# SuperGreatPI_v03.net
KiCad netlist of a schematic drawn in EAGLE
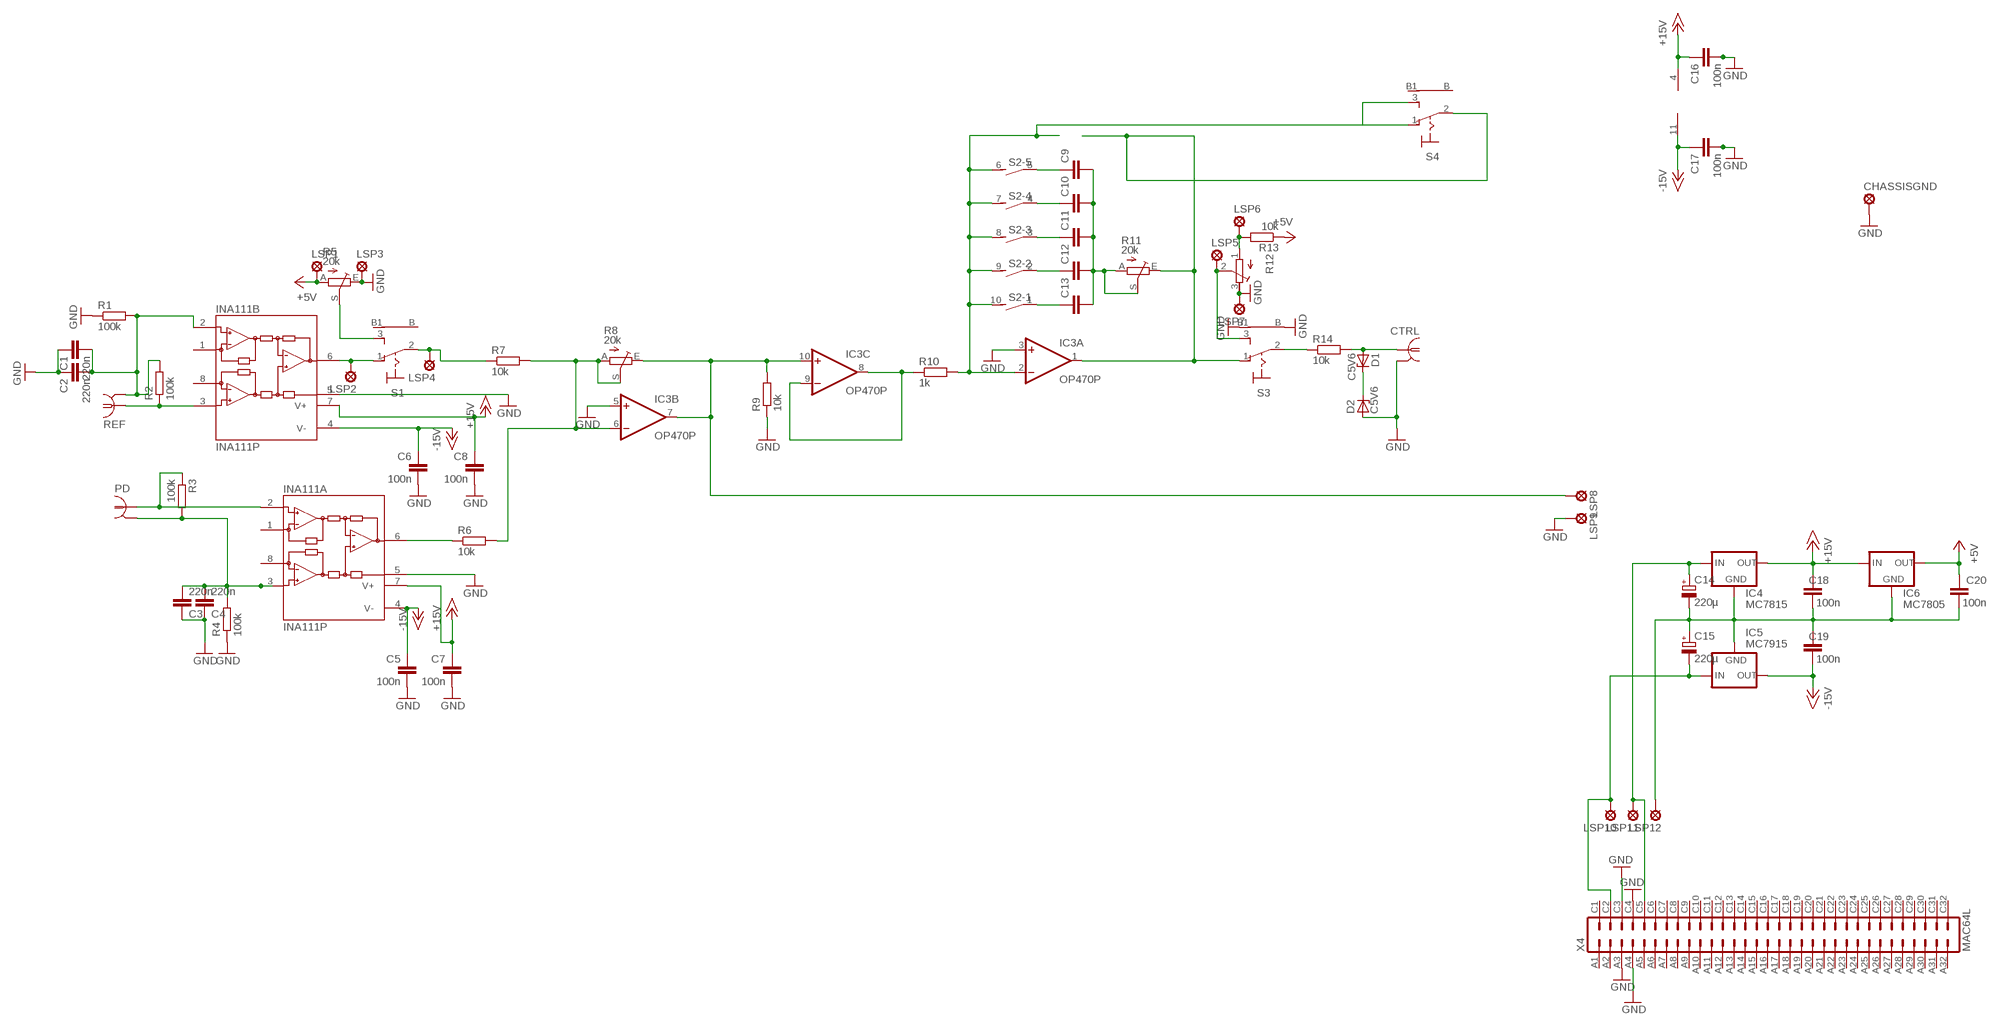
[diagram p0: schematic, sheet 1]

(export (version "E")
  (design (tool "Eeschema 10.0.6"))
  (components
    (comp (ref "C1")
      (value "220n")
      (footprint "eagle-import:C025-024X044")
      (libsource (lib "eagle-import") (part "C-EU025-024X044"))
    )
    (comp (ref "C2")
      (value "220n")
      (footprint "eagle-import:C025-024X044")
      (libsource (lib "eagle-import") (part "C-EU025-024X044"))
    )
    (comp (ref "C3")
      (value "220n")
      (footprint "eagle-import:C025-024X044")
      (libsource (lib "eagle-import") (part "C-EU025-024X044"))
    )
    (comp (ref "C4")
      (value "220n")
      (footprint "eagle-import:C025-024X044")
      (libsource (lib "eagle-import") (part "C-EU025-024X044"))
    )
    (comp (ref "C5")
      (value "100n")
      (footprint "eagle-import:C025-024X044")
      (libsource (lib "eagle-import") (part "C-EU025-024X044"))
    )
    (comp (ref "C6")
      (value "100n")
      (footprint "eagle-import:C025-024X044")
      (libsource (lib "eagle-import") (part "C-EU025-024X044"))
    )
    (comp (ref "C7")
      (value "100n")
      (footprint "eagle-import:C025-024X044")
      (libsource (lib "eagle-import") (part "C-EU025-024X044"))
    )
    (comp (ref "C8")
      (value "100n")
      (footprint "eagle-import:C025-024X044")
      (libsource (lib "eagle-import") (part "C-EU025-024X044"))
    )
    (comp (ref "C9")
      (value "C-EU050-025X075")
      (footprint "eagle-import:C050-025X075")
      (libsource (lib "eagle-import") (part "C-EU050-025X075"))
    )
    (comp (ref "C10")
      (value "C-EU050-025X075")
      (footprint "eagle-import:C050-025X075")
      (libsource (lib "eagle-import") (part "C-EU050-025X075"))
    )
    (comp (ref "C11")
      (value "C-EU050-025X075")
      (footprint "eagle-import:C050-025X075")
      (libsource (lib "eagle-import") (part "C-EU050-025X075"))
    )
    (comp (ref "C12")
      (value "C-EU050-025X075")
      (footprint "eagle-import:C050-025X075")
      (libsource (lib "eagle-import") (part "C-EU050-025X075"))
    )
    (comp (ref "C13")
      (value "C-EU050-025X075")
      (footprint "eagle-import:C050-025X075")
      (libsource (lib "eagle-import") (part "C-EU050-025X075"))
    )
    (comp (ref "C14")
      (value "220µ")
      (footprint "eagle-import:E3,5-8")
      (libsource (lib "eagle-import") (part "CPOL-EUE3.5-8"))
    )
    (comp (ref "C15")
      (value "220µ")
      (footprint "eagle-import:E3,5-8")
      (libsource (lib "eagle-import") (part "CPOL-EUE3.5-8"))
    )
    (comp (ref "C16")
      (value "100n")
      (footprint "eagle-import:C025-024X044")
      (libsource (lib "eagle-import") (part "C-EU025-024X044"))
    )
    (comp (ref "C17")
      (value "100n")
      (footprint "eagle-import:C025-024X044")
      (libsource (lib "eagle-import") (part "C-EU025-024X044"))
    )
    (comp (ref "C18")
      (value "100n")
      (footprint "eagle-import:C025-024X044")
      (libsource (lib "eagle-import") (part "C-EU025-024X044"))
    )
    (comp (ref "C19")
      (value "100n")
      (footprint "eagle-import:C025-024X044")
      (libsource (lib "eagle-import") (part "C-EU025-024X044"))
    )
    (comp (ref "C20")
      (value "100n")
      (footprint "eagle-import:C025-024X044")
      (libsource (lib "eagle-import") (part "C-EU025-024X044"))
    )
    (comp (ref "CHASSISGND")
      (value "MCS08")
      (footprint "eagle-import:MCS08")
      (libsource (lib "eagle-import") (part "MCS08"))
    )
    (comp (ref "CTRL")
      (value "1-227161-0")
      (footprint "eagle-import:AMP_227161")
      (libsource (lib "eagle-import") (part "?2271611--0"))
    )
    (comp (ref "D1")
      (value "C5V6")
      (footprint "eagle-import:DO34Z7")
      (libsource (lib "eagle-import") (part "BZX90"))
    )
    (comp (ref "D2")
      (value "C5V6")
      (footprint "eagle-import:DO34Z7")
      (libsource (lib "eagle-import") (part "BZX90"))
    )
    (comp (ref "IC3")
      (value "OP470P")
      (footprint "eagle-import:DIL14")
      (libsource (lib "eagle-import") (part "OP470P"))
    )
    (comp (ref "IC4")
      (value "MC7815")
      (footprint "eagle-import:78XXS")
      (libsource (lib "eagle-import") (part "78XXS"))
    )
    (comp (ref "IC5")
      (value "MC7915")
      (footprint "eagle-import:79XXS")
      (libsource (lib "eagle-import") (part "79XXS"))
    )
    (comp (ref "IC6")
      (value "MC7805")
      (footprint "eagle-import:78XXS")
      (libsource (lib "eagle-import") (part "78XXS"))
    )
    (comp (ref "INA111A")
      (value "INA111P")
      (footprint "eagle-import:DIL08")
      (libsource (lib "eagle-import") (part "INA111P"))
    )
    (comp (ref "INA111B")
      (value "INA111P")
      (footprint "eagle-import:DIL08")
      (libsource (lib "eagle-import") (part "INA111P"))
    )
    (comp (ref "LSP1")
      (value "MCS08")
      (footprint "eagle-import:MCS08")
      (libsource (lib "eagle-import") (part "MCS08"))
    )
    (comp (ref "LSP2")
      (value "MCS08")
      (footprint "eagle-import:MCS08")
      (libsource (lib "eagle-import") (part "MCS08"))
    )
    (comp (ref "LSP3")
      (value "MCS08")
      (footprint "eagle-import:MCS08")
      (libsource (lib "eagle-import") (part "MCS08"))
    )
    (comp (ref "LSP4")
      (value "MCS08")
      (footprint "eagle-import:MCS08")
      (libsource (lib "eagle-import") (part "MCS08"))
    )
    (comp (ref "LSP5")
      (value "MCS08")
      (footprint "eagle-import:MCS08")
      (libsource (lib "eagle-import") (part "MCS08"))
    )
    (comp (ref "LSP6")
      (value "MCS08")
      (footprint "eagle-import:MCS08")
      (libsource (lib "eagle-import") (part "MCS08"))
    )
    (comp (ref "LSP7")
      (value "MCS08")
      (footprint "eagle-import:MCS08")
      (libsource (lib "eagle-import") (part "MCS08"))
    )
    (comp (ref "LSP8")
      (value "MCS08")
      (footprint "eagle-import:MCS08")
      (libsource (lib "eagle-import") (part "MCS08"))
    )
    (comp (ref "LSP9")
      (value "MCS08")
      (footprint "eagle-import:MCS08")
      (libsource (lib "eagle-import") (part "MCS08"))
    )
    (comp (ref "LSP10")
      (value "-18V")
      (footprint "eagle-import:MCS08")
      (libsource (lib "eagle-import") (part "MCS08"))
    )
    (comp (ref "LSP11")
      (value "-18V")
      (footprint "eagle-import:MCS08")
      (libsource (lib "eagle-import") (part "MCS08"))
    )
    (comp (ref "LSP12")
      (value "GND")
      (footprint "eagle-import:MCS08")
      (libsource (lib "eagle-import") (part "MCS08"))
    )
    (comp (ref "PD")
      (value "1-227161-0")
      (footprint "eagle-import:AMP_227161")
      (libsource (lib "eagle-import") (part "?2271611--0"))
    )
    (comp (ref "R1")
      (value "100k")
      (footprint "eagle-import:0207_2V")
      (libsource (lib "eagle-import") (part "R-EU_0207/2V"))
    )
    (comp (ref "R2")
      (value "100k")
      (footprint "eagle-import:0207_2V")
      (libsource (lib "eagle-import") (part "R-EU_0207/2V"))
    )
    (comp (ref "R3")
      (value "100k")
      (footprint "eagle-import:0207_2V")
      (libsource (lib "eagle-import") (part "R-EU_0207/2V"))
    )
    (comp (ref "R4")
      (value "100k")
      (footprint "eagle-import:0207_2V")
      (libsource (lib "eagle-import") (part "R-EU_0207/2V"))
    )
    (comp (ref "R5")
      (value "20k")
      (footprint "eagle-import:PT-SPIN")
      (libsource (lib "eagle-import") (part "TRIM_EU-PTSPIN"))
    )
    (comp (ref "R6")
      (value "10k")
      (footprint "eagle-import:0207_10")
      (libsource (lib "eagle-import") (part "R-EU_0207/10"))
    )
    (comp (ref "R7")
      (value "10k")
      (footprint "eagle-import:0207_10")
      (libsource (lib "eagle-import") (part "R-EU_0207/10"))
    )
    (comp (ref "R8")
      (value "20k")
      (footprint "eagle-import:PT-SPIN")
      (libsource (lib "eagle-import") (part "TRIM_EU-PTSPIN"))
    )
    (comp (ref "R9")
      (value "10k")
      (footprint "eagle-import:0207_10")
      (libsource (lib "eagle-import") (part "R-EU_0207/10"))
    )
    (comp (ref "R10")
      (value "1k")
      (footprint "eagle-import:0207_10")
      (libsource (lib "eagle-import") (part "R-EU_0207/10"))
    )
    (comp (ref "R11")
      (value "20k")
      (footprint "eagle-import:PT-SPIN")
      (libsource (lib "eagle-import") (part "TRIM_EU-PTSPIN"))
    )
    (comp (ref "R12")
      (value "R-TRIMM3299W")
      (footprint "eagle-import:RTRIM3299W")
      (libsource (lib "eagle-import") (part "R-TRIMM3299W"))
    )
    (comp (ref "R13")
      (value "10k")
      (footprint "eagle-import:0207_10")
      (libsource (lib "eagle-import") (part "R-EU_0207/10"))
    )
    (comp (ref "R14")
      (value "10k")
      (footprint "eagle-import:0207_10")
      (libsource (lib "eagle-import") (part "R-EU_0207/10"))
    )
    (comp (ref "REF")
      (value "1-227161-0")
      (footprint "eagle-import:AMP_227161")
      (libsource (lib "eagle-import") (part "?2271611--0"))
    )
    (comp (ref "S1")
      (value "LPV-1")
      (footprint "eagle-import:LPV-1")
      (libsource (lib "eagle-import") (part "LPV-1"))
    )
    (comp (ref "S2")
      (value "DS05E")
      (footprint "eagle-import:DS-05")
      (libsource (lib "eagle-import") (part "DS05E"))
    )
    (comp (ref "S3")
      (value "LPV-1")
      (footprint "eagle-import:LPV-1")
      (libsource (lib "eagle-import") (part "LPV-1"))
    )
    (comp (ref "S4")
      (value "LPV-1")
      (footprint "eagle-import:LPV-1")
      (libsource (lib "eagle-import") (part "switch_380_LPV-1"))
    )
    (comp (ref "X4")
      (value "MAC64L")
      (footprint "eagle-import:MAC64L")
      (libsource (lib "eagle-import") (part "MAC64L"))
    )
  )
  (nets
    (net (code "1") (name "+5V") (class "Default")
      (node (ref "C20") (pin "1") (pinfunction "1_1") (pintype "passive"))
      (node (ref "IC6") (pin "OUT") (pinfunction "OUT_OUT") (pintype "passive"))
      (node (ref "LSP1") (pin "MP") (pinfunction "MP_MP") (pintype "passive"))
      (node (ref "R13") (pin "1") (pinfunction "1_1") (pintype "passive"))
      (node (ref "R5") (pin "A") (pinfunction "A_A") (pintype "passive"))
    )
    (net (code "2") (name "+15V") (class "Default")
      (node (ref "C16") (pin "1") (pinfunction "1_1") (pintype "passive"))
      (node (ref "C18") (pin "1") (pinfunction "1_1") (pintype "passive"))
      (node (ref "C7") (pin "1") (pinfunction "1_1") (pintype "passive"))
      (node (ref "C8") (pin "1") (pinfunction "1_1") (pintype "passive"))
      (node (ref "IC3") (pin "4") (pinfunction "V+_4") (pintype "power_in"))
      (node (ref "IC4") (pin "OUT") (pinfunction "OUT_OUT") (pintype "passive"))
      (node (ref "IC6") (pin "IN") (pinfunction "IN_IN") (pintype "input"))
      (node (ref "INA111A") (pin "7") (pinfunction "V+_7") (pintype "power_in"))
      (node (ref "INA111B") (pin "7") (pinfunction "V+_7") (pintype "power_in"))
    )
    (net (code "3") (name "-15V") (class "Default")
      (node (ref "C17") (pin "1") (pinfunction "1_1") (pintype "passive"))
      (node (ref "C19") (pin "2") (pinfunction "2_2") (pintype "passive"))
      (node (ref "C5") (pin "1") (pinfunction "1_1") (pintype "passive"))
      (node (ref "C6") (pin "1") (pinfunction "1_1") (pintype "passive"))
      (node (ref "IC3") (pin "11") (pinfunction "V-_11") (pintype "power_in"))
      (node (ref "IC5") (pin "OUT") (pinfunction "OUT_OUT") (pintype "passive"))
      (node (ref "INA111A") (pin "4") (pinfunction "V-_4") (pintype "power_in"))
      (node (ref "INA111B") (pin "4") (pinfunction "V-_4") (pintype "power_in"))
    )
    (net (code "4") (name "GND") (class "Default")
      (node (ref "C1") (pin "1") (pinfunction "1_1") (pintype "passive"))
      (node (ref "C14") (pin "-") (pinfunction "-_-") (pintype "passive"))
      (node (ref "C15") (pin "+") (pinfunction "+_+") (pintype "passive"))
      (node (ref "C16") (pin "2") (pinfunction "2_2") (pintype "passive"))
      (node (ref "C17") (pin "2") (pinfunction "2_2") (pintype "passive"))
      (node (ref "C18") (pin "2") (pinfunction "2_2") (pintype "passive"))
      (node (ref "C19") (pin "1") (pinfunction "1_1") (pintype "passive"))
      (node (ref "C2") (pin "1") (pinfunction "1_1") (pintype "passive"))
      (node (ref "C20") (pin "2") (pinfunction "2_2") (pintype "passive"))
      (node (ref "C3") (pin "1") (pinfunction "1_1") (pintype "passive"))
      (node (ref "C4") (pin "1") (pinfunction "1_1") (pintype "passive"))
      (node (ref "C5") (pin "2") (pinfunction "2_2") (pintype "passive"))
      (node (ref "C6") (pin "2") (pinfunction "2_2") (pintype "passive"))
      (node (ref "C7") (pin "2") (pinfunction "2_2") (pintype "passive"))
      (node (ref "C8") (pin "2") (pinfunction "2_2") (pintype "passive"))
      (node (ref "CHASSISGND") (pin "MP") (pinfunction "MP_MP") (pintype "passive"))
      (node (ref "CTRL") (pin "2") (pinfunction "GND_2") (pintype "power_in"))
      (node (ref "D2") (pin "A") (pinfunction "A_A") (pintype "passive"))
      (node (ref "IC3") (pin "3") (pinfunction "+IN_3") (pintype "input"))
      (node (ref "IC3") (pin "5") (pinfunction "+IN_5") (pintype "input"))
      (node (ref "IC4") (pin "GND") (pinfunction "GND_GND") (pintype "input"))
      (node (ref "IC5") (pin "GND") (pinfunction "GND_GND") (pintype "input"))
      (node (ref "IC6") (pin "GND") (pinfunction "GND_GND") (pintype "input"))
      (node (ref "INA111A") (pin "5") (pinfunction "REF_5") (pintype "passive"))
      (node (ref "INA111B") (pin "5") (pinfunction "REF_5") (pintype "passive"))
      (node (ref "LSP12") (pin "MP") (pinfunction "MP_MP") (pintype "passive"))
      (node (ref "LSP3") (pin "MP") (pinfunction "MP_MP") (pintype "passive"))
      (node (ref "LSP7") (pin "MP") (pinfunction "MP_MP") (pintype "passive"))
      (node (ref "LSP9") (pin "MP") (pinfunction "MP_MP") (pintype "passive"))
      (node (ref "R1") (pin "1") (pinfunction "1_1") (pintype "passive"))
      (node (ref "R12") (pin "3") (pinfunction "E_3") (pintype "passive"))
      (node (ref "R4") (pin "1") (pinfunction "1_1") (pintype "passive"))
      (node (ref "R5") (pin "E") (pinfunction "E_E") (pintype "passive"))
      (node (ref "R9") (pin "1") (pinfunction "1_1") (pintype "passive"))
      (node (ref "S3") (pin "B") (pinfunction "B_B") (pintype "passive"))
      (node (ref "S3") (pin "B1") (pinfunction "B1_B1") (pintype "passive"))
      (node (ref "X4") (pin "A3") (pinfunction "A3_A3") (pintype "passive"))
      (node (ref "X4") (pin "A4") (pinfunction "A4_A4") (pintype "passive"))
      (node (ref "X4") (pin "C3") (pinfunction "C3_C3") (pintype "passive"))
      (node (ref "X4") (pin "C4") (pinfunction "C4_C4") (pintype "passive"))
    )
    (net (code "5") (name "Net-(C10-Pad2)") (class "Default")
      (node (ref "C10") (pin "2") (pinfunction "2_2") (pintype "passive"))
      (node (ref "C11") (pin "2") (pinfunction "2_2") (pintype "passive"))
      (node (ref "C12") (pin "2") (pinfunction "2_2") (pintype "passive"))
      (node (ref "C13") (pin "2") (pinfunction "2_2") (pintype "passive"))
      (node (ref "C9") (pin "2") (pinfunction "2_2") (pintype "passive"))
      (node (ref "R11") (pin "A") (pinfunction "A_A") (pintype "passive"))
      (node (ref "R11") (pin "S") (pinfunction "S_S") (pintype "passive"))
    )
    (net (code "6") (name "Net-(C13-Pad1)") (class "Default")
      (node (ref "C13") (pin "1") (pinfunction "1_1") (pintype "passive"))
      (node (ref "S2") (pin "1") (pinfunction "1_1") (pintype "passive"))
    )
    (net (code "7") (name "Net-(C14-Pad+)") (class "Default")
      (node (ref "C14") (pin "+") (pinfunction "+_+") (pintype "passive"))
      (node (ref "IC4") (pin "IN") (pinfunction "IN_IN") (pintype "input"))
      (node (ref "LSP11") (pin "MP") (pinfunction "MP_MP") (pintype "passive"))
      (node (ref "X4") (pin "C5") (pinfunction "C5_C5") (pintype "passive"))
    )
    (net (code "8") (name "Net-(C15-Pad-)") (class "Default")
      (node (ref "C15") (pin "-") (pinfunction "-_-") (pintype "passive"))
      (node (ref "IC5") (pin "IN") (pinfunction "IN_IN") (pintype "input"))
      (node (ref "LSP10") (pin "MP") (pinfunction "MP_MP") (pintype "passive"))
      (node (ref "X4") (pin "C2") (pinfunction "C2_C2") (pintype "passive"))
    )
    (net (code "9") (name "Net-(CTRL-Pad1)") (class "Default")
      (node (ref "CTRL") (pin "1") (pinfunction "1_1") (pintype "passive"))
      (node (ref "D1") (pin "A") (pinfunction "A_A") (pintype "passive"))
      (node (ref "R14") (pin "2") (pinfunction "2_2") (pintype "passive"))
    )
    (net (code "10") (name "Net-(D1-PadC)") (class "Default")
      (node (ref "D1") (pin "C") (pinfunction "C_C") (pintype "passive"))
      (node (ref "D2") (pin "C") (pinfunction "C_C") (pintype "passive"))
    )
    (net (code "11") (name "Net-(IC3A--IN)") (class "Default")
      (node (ref "IC3") (pin "2") (pinfunction "-IN_2") (pintype "input"))
      (node (ref "R10") (pin "2") (pinfunction "2_2") (pintype "passive"))
      (node (ref "S2") (pin "10") (pinfunction "2_10") (pintype "passive"))
      (node (ref "S2") (pin "6") (pinfunction "2_6") (pintype "passive"))
      (node (ref "S2") (pin "7") (pinfunction "2_7") (pintype "passive"))
      (node (ref "S2") (pin "8") (pinfunction "2_8") (pintype "passive"))
      (node (ref "S2") (pin "9") (pinfunction "2_9") (pintype "passive"))
      (node (ref "S4") (pin "1") (pinfunction "O_1") (pintype "passive"))
      (node (ref "S4") (pin "3") (pinfunction "S_3") (pintype "passive"))
    )
    (net (code "12") (name "Net-(IC3A-OUT)") (class "Default")
      (node (ref "IC3") (pin "1") (pinfunction "OUT_1") (pintype "output"))
      (node (ref "R11") (pin "E") (pinfunction "E_E") (pintype "passive"))
      (node (ref "S3") (pin "1") (pinfunction "O_1") (pintype "passive"))
      (node (ref "S4") (pin "2") (pinfunction "P_2") (pintype "passive"))
    )
    (net (code "13") (name "Net-(IC3B--IN)") (class "Default")
      (node (ref "IC3") (pin "6") (pinfunction "-IN_6") (pintype "input"))
      (node (ref "R6") (pin "2") (pinfunction "2_2") (pintype "passive"))
      (node (ref "R7") (pin "2") (pinfunction "2_2") (pintype "passive"))
      (node (ref "R8") (pin "A") (pinfunction "A_A") (pintype "passive"))
      (node (ref "R8") (pin "S") (pinfunction "S_S") (pintype "passive"))
    )
    (net (code "14") (name "Net-(IC3B-OUT)") (class "Default")
      (node (ref "IC3") (pin "10") (pinfunction "+IN_10") (pintype "input"))
      (node (ref "IC3") (pin "7") (pinfunction "OUT_7") (pintype "output"))
      (node (ref "LSP8") (pin "MP") (pinfunction "MP_MP") (pintype "passive"))
      (node (ref "R8") (pin "E") (pinfunction "E_E") (pintype "passive"))
      (node (ref "R9") (pin "2") (pinfunction "2_2") (pintype "passive"))
    )
    (net (code "15") (name "Net-(IC3C--IN)") (class "Default")
      (node (ref "IC3") (pin "8") (pinfunction "OUT_8") (pintype "output"))
      (node (ref "IC3") (pin "9") (pinfunction "-IN_9") (pintype "input"))
      (node (ref "R10") (pin "1") (pinfunction "1_1") (pintype "passive"))
    )
    (net (code "16") (name "Net-(INA111A-+IN)") (class "Default")
      (node (ref "C3") (pin "2") (pinfunction "2_2") (pintype "passive"))
      (node (ref "C4") (pin "2") (pinfunction "2_2") (pintype "passive"))
      (node (ref "INA111A") (pin "3") (pinfunction "+IN_3") (pintype "input"))
      (node (ref "PD") (pin "2") (pinfunction "GND_2") (pintype "power_in"))
      (node (ref "R3") (pin "2") (pinfunction "2_2") (pintype "passive"))
      (node (ref "R4") (pin "2") (pinfunction "2_2") (pintype "passive"))
    )
    (net (code "17") (name "Net-(INA111A--IN)") (class "Default")
      (node (ref "INA111A") (pin "2") (pinfunction "-IN_2") (pintype "input"))
      (node (ref "PD") (pin "1") (pinfunction "1_1") (pintype "passive"))
      (node (ref "R3") (pin "1") (pinfunction "1_1") (pintype "passive"))
    )
    (net (code "18") (name "Net-(INA111A-OUT)") (class "Default")
      (node (ref "INA111A") (pin "6") (pinfunction "OUT_6") (pintype "output"))
      (node (ref "R6") (pin "1") (pinfunction "1_1") (pintype "passive"))
    )
    (net (code "19") (name "Net-(INA111B-+IN)") (class "Default")
      (node (ref "INA111B") (pin "3") (pinfunction "+IN_3") (pintype "input"))
      (node (ref "R2") (pin "1") (pinfunction "1_1") (pintype "passive"))
      (node (ref "REF") (pin "1") (pinfunction "1_1") (pintype "passive"))
    )
    (net (code "20") (name "Net-(INA111B--IN)") (class "Default")
      (node (ref "C1") (pin "2") (pinfunction "2_2") (pintype "passive"))
      (node (ref "C2") (pin "2") (pinfunction "2_2") (pintype "passive"))
      (node (ref "INA111B") (pin "2") (pinfunction "-IN_2") (pintype "input"))
      (node (ref "R1") (pin "2") (pinfunction "2_2") (pintype "passive"))
      (node (ref "R2") (pin "2") (pinfunction "2_2") (pintype "passive"))
      (node (ref "REF") (pin "2") (pinfunction "GND_2") (pintype "power_in"))
    )
    (net (code "21") (name "Net-(INA111B-OUT)") (class "Default")
      (node (ref "INA111B") (pin "6") (pinfunction "OUT_6") (pintype "output"))
      (node (ref "LSP2") (pin "MP") (pinfunction "MP_MP") (pintype "passive"))
      (node (ref "S1") (pin "1") (pinfunction "O_1") (pintype "passive"))
    )
    (net (code "22") (name "Net-(R12-A)") (class "Default")
      (node (ref "LSP6") (pin "MP") (pinfunction "MP_MP") (pintype "passive"))
      (node (ref "R12") (pin "1") (pinfunction "A_1") (pintype "passive"))
      (node (ref "R13") (pin "2") (pinfunction "2_2") (pintype "passive"))
    )
    (net (code "23") (name "Net-(R12-S)") (class "Default")
      (node (ref "LSP5") (pin "MP") (pinfunction "MP_MP") (pintype "passive"))
      (node (ref "R12") (pin "2") (pinfunction "S_2") (pintype "passive"))
      (node (ref "S3") (pin "3") (pinfunction "S_3") (pintype "passive"))
    )
    (net (code "24") (name "Net-(S1-P)") (class "Default")
      (node (ref "LSP4") (pin "MP") (pinfunction "MP_MP") (pintype "passive"))
      (node (ref "R7") (pin "1") (pinfunction "1_1") (pintype "passive"))
      (node (ref "S1") (pin "2") (pinfunction "P_2") (pintype "passive"))
    )
    (net (code "25") (name "Net-(S1-S)") (class "Default")
      (node (ref "R5") (pin "S") (pinfunction "S_S") (pintype "passive"))
      (node (ref "S1") (pin "3") (pinfunction "S_3") (pintype "passive"))
    )
    (net (code "26") (name "Net-(S2B-1)") (class "Default")
      (node (ref "C12") (pin "1") (pinfunction "1_1") (pintype "passive"))
      (node (ref "S2") (pin "2") (pinfunction "1_2") (pintype "passive"))
    )
    (net (code "27") (name "Net-(S2C-1)") (class "Default")
      (node (ref "C11") (pin "1") (pinfunction "1_1") (pintype "passive"))
      (node (ref "S2") (pin "3") (pinfunction "1_3") (pintype "passive"))
    )
    (net (code "28") (name "Net-(S2D-1)") (class "Default")
      (node (ref "C10") (pin "1") (pinfunction "1_1") (pintype "passive"))
      (node (ref "S2") (pin "4") (pinfunction "1_4") (pintype "passive"))
    )
    (net (code "29") (name "Net-(S2E-1)") (class "Default")
      (node (ref "C9") (pin "1") (pinfunction "1_1") (pintype "passive"))
      (node (ref "S2") (pin "5") (pinfunction "1_5") (pintype "passive"))
    )
    (net (code "30") (name "Net-(S3-P)") (class "Default")
      (node (ref "R14") (pin "1") (pinfunction "1_1") (pintype "passive"))
      (node (ref "S3") (pin "2") (pinfunction "P_2") (pintype "passive"))
    )
    (net (code "31") (name "unconnected-(INA111A-RG-Pad1)") (class "Default")
      (node (ref "INA111A") (pin "1") (pinfunction "RG_1") (pintype "passive"))
    )
    (net (code "32") (name "unconnected-(INA111A-RG-Pad8)") (class "Default")
      (node (ref "INA111A") (pin "8") (pinfunction "RG_8") (pintype "passive"))
    )
    (net (code "33") (name "unconnected-(INA111B-RG-Pad1)") (class "Default")
      (node (ref "INA111B") (pin "1") (pinfunction "RG_1") (pintype "passive"))
    )
    (net (code "34") (name "unconnected-(INA111B-RG-Pad8)") (class "Default")
      (node (ref "INA111B") (pin "8") (pinfunction "RG_8") (pintype "passive"))
    )
    (net (code "35") (name "unconnected-(S1-PadB)") (class "Default")
      (node (ref "S1") (pin "B") (pinfunction "B_B") (pintype "passive"))
    )
    (net (code "36") (name "unconnected-(S1-PadB1)") (class "Default")
      (node (ref "S1") (pin "B1") (pinfunction "B1_B1") (pintype "passive"))
    )
    (net (code "37") (name "unconnected-(S4-PadB)") (class "Default")
      (node (ref "S4") (pin "B") (pinfunction "B_B") (pintype "passive"))
    )
    (net (code "38") (name "unconnected-(S4-PadB1)") (class "Default")
      (node (ref "S4") (pin "B1") (pinfunction "B1_B1") (pintype "passive"))
    )
    (net (code "39") (name "unconnected-(X4-PadA1)") (class "Default")
      (node (ref "X4") (pin "A1") (pinfunction "A1_A1") (pintype "passive"))
    )
    (net (code "40") (name "unconnected-(X4-PadA2)") (class "Default")
      (node (ref "X4") (pin "A2") (pinfunction "A2_A2") (pintype "passive"))
    )
    (net (code "41") (name "unconnected-(X4-PadA5)") (class "Default")
      (node (ref "X4") (pin "A5") (pinfunction "A5_A5") (pintype "passive"))
    )
    (net (code "42") (name "unconnected-(X4-PadA6)") (class "Default")
      (node (ref "X4") (pin "A6") (pinfunction "A6_A6") (pintype "passive"))
    )
    (net (code "43") (name "unconnected-(X4-PadA7)") (class "Default")
      (node (ref "X4") (pin "A7") (pinfunction "A7_A7") (pintype "passive"))
    )
    (net (code "44") (name "unconnected-(X4-PadA8)") (class "Default")
      (node (ref "X4") (pin "A8") (pinfunction "A8_A8") (pintype "passive"))
    )
    (net (code "45") (name "unconnected-(X4-PadA9)") (class "Default")
      (node (ref "X4") (pin "A9") (pinfunction "A9_A9") (pintype "passive"))
    )
    (net (code "46") (name "unconnected-(X4-PadA10)") (class "Default")
      (node (ref "X4") (pin "A10") (pinfunction "A10_A10") (pintype "passive"))
    )
    (net (code "47") (name "unconnected-(X4-PadA11)") (class "Default")
      (node (ref "X4") (pin "A11") (pinfunction "A11_A11") (pintype "passive"))
    )
    (net (code "48") (name "unconnected-(X4-PadA12)") (class "Default")
      (node (ref "X4") (pin "A12") (pinfunction "A12_A12") (pintype "passive"))
    )
    (net (code "49") (name "unconnected-(X4-PadA13)") (class "Default")
      (node (ref "X4") (pin "A13") (pinfunction "A13_A13") (pintype "passive"))
    )
    (net (code "50") (name "unconnected-(X4-PadA14)") (class "Default")
      (node (ref "X4") (pin "A14") (pinfunction "A14_A14") (pintype "passive"))
    )
    (net (code "51") (name "unconnected-(X4-PadA15)") (class "Default")
      (node (ref "X4") (pin "A15") (pinfunction "A15_A15") (pintype "passive"))
    )
    (net (code "52") (name "unconnected-(X4-PadA16)") (class "Default")
      (node (ref "X4") (pin "A16") (pinfunction "A16_A16") (pintype "passive"))
    )
    (net (code "53") (name "unconnected-(X4-PadA17)") (class "Default")
      (node (ref "X4") (pin "A17") (pinfunction "A17_A17") (pintype "passive"))
    )
    (net (code "54") (name "unconnected-(X4-PadA18)") (class "Default")
      (node (ref "X4") (pin "A18") (pinfunction "A18_A18") (pintype "passive"))
    )
    (net (code "55") (name "unconnected-(X4-PadA19)") (class "Default")
      (node (ref "X4") (pin "A19") (pinfunction "A19_A19") (pintype "passive"))
    )
    (net (code "56") (name "unconnected-(X4-PadA20)") (class "Default")
      (node (ref "X4") (pin "A20") (pinfunction "A20_A20") (pintype "passive"))
    )
    (net (code "57") (name "unconnected-(X4-PadA21)") (class "Default")
      (node (ref "X4") (pin "A21") (pinfunction "A21_A21") (pintype "passive"))
    )
    (net (code "58") (name "unconnected-(X4-PadA22)") (class "Default")
      (node (ref "X4") (pin "A22") (pinfunction "A22_A22") (pintype "passive"))
    )
    (net (code "59") (name "unconnected-(X4-PadA23)") (class "Default")
      (node (ref "X4") (pin "A23") (pinfunction "A23_A23") (pintype "passive"))
    )
    (net (code "60") (name "unconnected-(X4-PadA24)") (class "Default")
      (node (ref "X4") (pin "A24") (pinfunction "A24_A24") (pintype "passive"))
    )
    (net (code "61") (name "unconnected-(X4-PadA25)") (class "Default")
      (node (ref "X4") (pin "A25") (pinfunction "A25_A25") (pintype "passive"))
    )
    (net (code "62") (name "unconnected-(X4-PadA26)") (class "Default")
      (node (ref "X4") (pin "A26") (pinfunction "A26_A26") (pintype "passive"))
    )
    (net (code "63") (name "unconnected-(X4-PadA27)") (class "Default")
      (node (ref "X4") (pin "A27") (pinfunction "A27_A27") (pintype "passive"))
    )
    (net (code "64") (name "unconnected-(X4-PadA28)") (class "Default")
      (node (ref "X4") (pin "A28") (pinfunction "A28_A28") (pintype "passive"))
    )
    (net (code "65") (name "unconnected-(X4-PadA29)") (class "Default")
      (node (ref "X4") (pin "A29") (pinfunction "A29_A29") (pintype "passive"))
    )
    (net (code "66") (name "unconnected-(X4-PadA30)") (class "Default")
      (node (ref "X4") (pin "A30") (pinfunction "A30_A30") (pintype "passive"))
    )
    (net (code "67") (name "unconnected-(X4-PadA31)") (class "Default")
      (node (ref "X4") (pin "A31") (pinfunction "A31_A31") (pintype "passive"))
    )
    (net (code "68") (name "unconnected-(X4-PadA32)") (class "Default")
      (node (ref "X4") (pin "A32") (pinfunction "A32_A32") (pintype "passive"))
    )
    (net (code "69") (name "unconnected-(X4-PadC1)") (class "Default")
      (node (ref "X4") (pin "C1") (pinfunction "C1_C1") (pintype "passive"))
    )
    (net (code "70") (name "unconnected-(X4-PadC6)") (class "Default")
      (node (ref "X4") (pin "C6") (pinfunction "C6_C6") (pintype "passive"))
    )
    (net (code "71") (name "unconnected-(X4-PadC7)") (class "Default")
      (node (ref "X4") (pin "C7") (pinfunction "C7_C7") (pintype "passive"))
    )
    (net (code "72") (name "unconnected-(X4-PadC8)") (class "Default")
      (node (ref "X4") (pin "C8") (pinfunction "C8_C8") (pintype "passive"))
    )
    (net (code "73") (name "unconnected-(X4-PadC9)") (class "Default")
      (node (ref "X4") (pin "C9") (pinfunction "C9_C9") (pintype "passive"))
    )
    (net (code "74") (name "unconnected-(X4-PadC10)") (class "Default")
      (node (ref "X4") (pin "C10") (pinfunction "C10_C10") (pintype "passive"))
    )
    (net (code "75") (name "unconnected-(X4-PadC11)") (class "Default")
      (node (ref "X4") (pin "C11") (pinfunction "C11_C11") (pintype "passive"))
    )
    (net (code "76") (name "unconnected-(X4-PadC12)") (class "Default")
      (node (ref "X4") (pin "C12") (pinfunction "C12_C12") (pintype "passive"))
    )
    (net (code "77") (name "unconnected-(X4-PadC13)") (class "Default")
      (node (ref "X4") (pin "C13") (pinfunction "C13_C13") (pintype "passive"))
    )
    (net (code "78") (name "unconnected-(X4-PadC14)") (class "Default")
      (node (ref "X4") (pin "C14") (pinfunction "C14_C14") (pintype "passive"))
    )
    (net (code "79") (name "unconnected-(X4-PadC15)") (class "Default")
      (node (ref "X4") (pin "C15") (pinfunction "C15_C15") (pintype "passive"))
    )
    (net (code "80") (name "unconnected-(X4-PadC16)") (class "Default")
      (node (ref "X4") (pin "C16") (pinfunction "C16_C16") (pintype "passive"))
    )
    (net (code "81") (name "unconnected-(X4-PadC17)") (class "Default")
      (node (ref "X4") (pin "C17") (pinfunction "C17_C17") (pintype "passive"))
    )
    (net (code "82") (name "unconnected-(X4-PadC18)") (class "Default")
      (node (ref "X4") (pin "C18") (pinfunction "C18_C18") (pintype "passive"))
    )
    (net (code "83") (name "unconnected-(X4-PadC19)") (class "Default")
      (node (ref "X4") (pin "C19") (pinfunction "C19_C19") (pintype "passive"))
    )
    (net (code "84") (name "unconnected-(X4-PadC20)") (class "Default")
      (node (ref "X4") (pin "C20") (pinfunction "C20_C20") (pintype "passive"))
    )
    (net (code "85") (name "unconnected-(X4-PadC21)") (class "Default")
      (node (ref "X4") (pin "C21") (pinfunction "C21_C21") (pintype "passive"))
    )
    (net (code "86") (name "unconnected-(X4-PadC22)") (class "Default")
      (node (ref "X4") (pin "C22") (pinfunction "C22_C22") (pintype "passive"))
    )
    (net (code "87") (name "unconnected-(X4-PadC23)") (class "Default")
      (node (ref "X4") (pin "C23") (pinfunction "C23_C23") (pintype "passive"))
    )
    (net (code "88") (name "unconnected-(X4-PadC24)") (class "Default")
      (node (ref "X4") (pin "C24") (pinfunction "C24_C24") (pintype "passive"))
    )
    (net (code "89") (name "unconnected-(X4-PadC25)") (class "Default")
      (node (ref "X4") (pin "C25") (pinfunction "C25_C25") (pintype "passive"))
    )
    (net (code "90") (name "unconnected-(X4-PadC26)") (class "Default")
      (node (ref "X4") (pin "C26") (pinfunction "C26_C26") (pintype "passive"))
    )
    (net (code "91") (name "unconnected-(X4-PadC27)") (class "Default")
      (node (ref "X4") (pin "C27") (pinfunction "C27_C27") (pintype "passive"))
    )
    (net (code "92") (name "unconnected-(X4-PadC28)") (class "Default")
      (node (ref "X4") (pin "C28") (pinfunction "C28_C28") (pintype "passive"))
    )
    (net (code "93") (name "unconnected-(X4-PadC29)") (class "Default")
      (node (ref "X4") (pin "C29") (pinfunction "C29_C29") (pintype "passive"))
    )
    (net (code "94") (name "unconnected-(X4-PadC30)") (class "Default")
      (node (ref "X4") (pin "C30") (pinfunction "C30_C30") (pintype "passive"))
    )
    (net (code "95") (name "unconnected-(X4-PadC31)") (class "Default")
      (node (ref "X4") (pin "C31") (pinfunction "C31_C31") (pintype "passive"))
    )
    (net (code "96") (name "unconnected-(X4-PadC32)") (class "Default")
      (node (ref "X4") (pin "C32") (pinfunction "C32_C32") (pintype "passive"))
    )
  )
)
